# CanLogger_V21.net
KiCad netlist of a schematic drawn in EAGLE
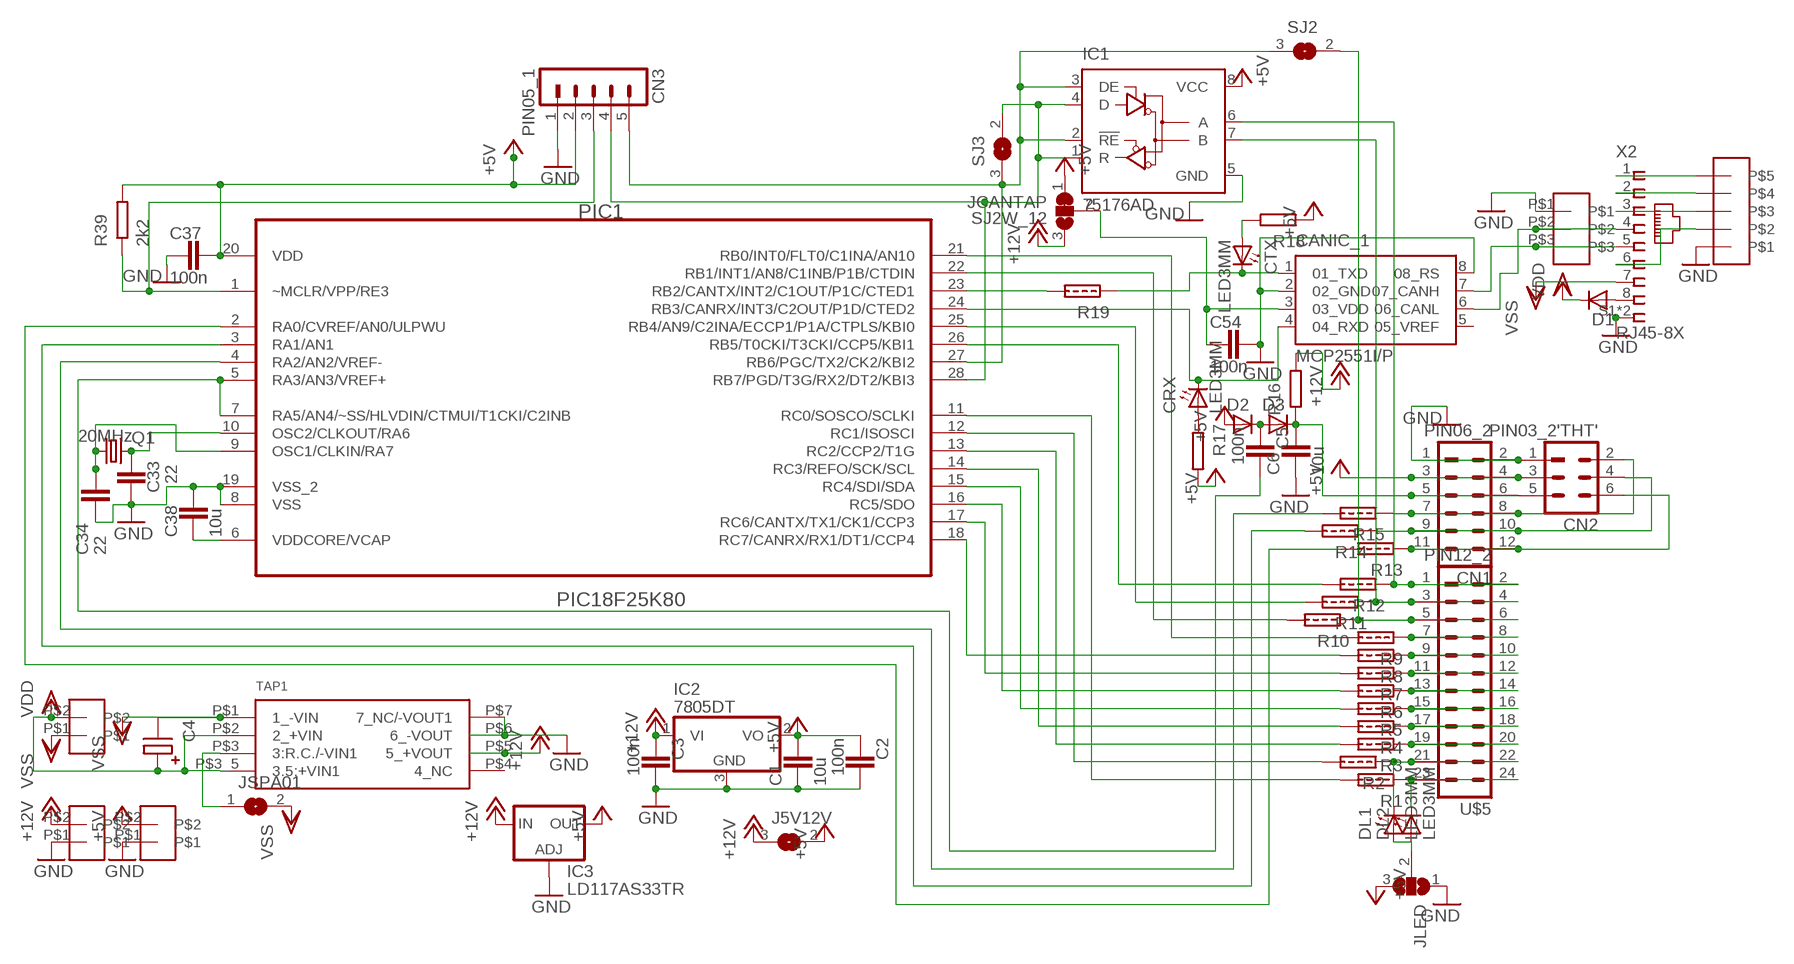
[diagram p0: schematic, sheet 1]

(export (version "E")
  (design (tool "Eeschema 10.0.6"))
  (components
    (comp (ref "C1")
      (value "10u")
      (footprint "eagle-import:R0805")
      (libsource (lib "eagle-import") (part "C0805"))
    )
    (comp (ref "C2")
      (value "100n")
      (footprint "eagle-import:R0805")
      (libsource (lib "eagle-import") (part "C0805"))
    )
    (comp (ref "C3")
      (value "100n")
      (footprint "eagle-import:R0805")
      (libsource (lib "eagle-import") (part "C0805"))
    )
    (comp (ref "C4")
      (value "C_EL1R05")
      (footprint "eagle-import:C_EL1RASZT05")
      (libsource (lib "eagle-import") (part "C_EL1R05"))
    )
    (comp (ref "C5")
      (value "100n")
      (footprint "eagle-import:R0805")
      (libsource (lib "eagle-import") (part "C0805"))
    )
    (comp (ref "C6")
      (value "10u")
      (footprint "eagle-import:R0805")
      (libsource (lib "eagle-import") (part "C0805"))
    )
    (comp (ref "C33")
      (value "22")
      (footprint "eagle-import:R0805")
      (libsource (lib "eagle-import") (part "C0805"))
    )
    (comp (ref "C34")
      (value "22")
      (footprint "eagle-import:R0805")
      (libsource (lib "eagle-import") (part "C0805"))
    )
    (comp (ref "C37")
      (value "100n")
      (footprint "eagle-import:R0805")
      (libsource (lib "eagle-import") (part "C0805"))
    )
    (comp (ref "C38")
      (value "10u")
      (footprint "eagle-import:R0805")
      (libsource (lib "eagle-import") (part "C0805"))
    )
    (comp (ref "C54")
      (value "100n")
      (footprint "eagle-import:R0805")
      (libsource (lib "eagle-import") (part "C0805"))
    )
    (comp (ref "CANIC_1")
      (value "MCP2551I/P")
      (footprint "eagle-import:DIL_8")
      (libsource (lib "eagle-import") (part "MCP2551I/P"))
    )
    (comp (ref "CN1")
      (value "PIN06_2")
      (footprint "eagle-import:PIN06_2")
      (libsource (lib "eagle-import") (part "PIN06_2"))
    )
    (comp (ref "CN2")
      (value "PIN03_2'THT'")
      (footprint "eagle-import:PIN03_2")
      (libsource (lib "eagle-import") (part "PIN03_2'THT'"))
    )
    (comp (ref "CN3")
      (value "PIN05_1")
      (footprint "eagle-import:PIN05_1")
      (libsource (lib "eagle-import") (part "PIN05_1"))
    )
    (comp (ref "CN_CAN")
      (value "FEHER_TUS_3")
      (footprint "eagle-import:FEHER_TUS_3")
      (libsource (lib "eagle-import") (part "FEHER_TUS_3"))
    )
    (comp (ref "CRX")
      (value "LED3MM")
      (footprint "eagle-import:LED3MM")
      (libsource (lib "eagle-import") (part "LED3MM"))
    )
    (comp (ref "CTX")
      (value "LED3MM")
      (footprint "eagle-import:LED3MM")
      (libsource (lib "eagle-import") (part "LED3MM"))
    )
    (comp (ref "D1")
      (value "D1RNAGY")
      (footprint "eagle-import:D1RASZTNAGY")
      (libsource (lib "eagle-import") (part "D1RNAGY"))
    )
    (comp (ref "D2")
      (value "D0805")
      (footprint "eagle-import:D0805")
      (libsource (lib "eagle-import") (part "D0805"))
    )
    (comp (ref "D3")
      (value "D0805")
      (footprint "eagle-import:D0805")
      (libsource (lib "eagle-import") (part "D0805"))
    )
    (comp (ref "DL1")
      (value "LED3MM")
      (footprint "eagle-import:LED3MM")
      (libsource (lib "eagle-import") (part "LED3MM"))
    )
    (comp (ref "DL2")
      (value "LED3MM")
      (footprint "eagle-import:LED3MM")
      (libsource (lib "eagle-import") (part "LED3MM"))
    )
    (comp (ref "IC1")
      (value "75176AD")
      (footprint "eagle-import:D_R-PDSO-G8")
      (libsource (lib "eagle-import") (part "75176AD"))
    )
    (comp (ref "IC2")
      (value "7805DT")
      (footprint "eagle-import:TO252")
      (libsource (lib "eagle-import") (part "78DT05"))
    )
    (comp (ref "IC3")
      (value "LD117AS33TR")
      (footprint "eagle-import:SOT223")
      (libsource (lib "eagle-import") (part "LD117A?S33TR"))
    )
    (comp (ref "J5V12V")
      (value "SJ")
      (footprint "eagle-import:SJ")
      (libsource (lib "eagle-import") (part "jumper2_SJ"))
    )
    (comp (ref "JCANTAP")
      (value "SJ2W_12")
      (footprint "eagle-import:SJ2_12")
      (libsource (lib "eagle-import") (part "SJ2W_12"))
    )
    (comp (ref "JLED")
      (value "SJ2W")
      (footprint "eagle-import:SJ2")
      (libsource (lib "eagle-import") (part "SJ2W"))
    )
    (comp (ref "JSPA01")
      (value "SJW")
      (footprint "eagle-import:SJW")
      (libsource (lib "eagle-import") (part "SJW"))
    )
    (comp (ref "PIC1")
      (value "PIC18F25K80")
      (footprint "eagle-import:SOIC127P1030X265-28N")
      (libsource (lib "eagle-import") (part "PIC18F25K80"))
    )
    (comp (ref "Q1")
      (value "20MHz")
      (footprint "eagle-import:XTAL_QS")
      (libsource (lib "eagle-import") (part "XTAL_2QS"))
    )
    (comp (ref "R1")
      (value "RNULL_EU0805")
      (footprint "eagle-import:R0805_C")
      (libsource (lib "eagle-import") (part "RNULL_EU0805"))
    )
    (comp (ref "R2")
      (value "RNULL_EU0805")
      (footprint "eagle-import:R0805_C")
      (libsource (lib "eagle-import") (part "RNULL_EU0805"))
    )
    (comp (ref "R3")
      (value "RNULL_EU0805")
      (footprint "eagle-import:R0805_C")
      (libsource (lib "eagle-import") (part "RNULL_EU0805"))
    )
    (comp (ref "R4")
      (value "RNULL_EU0805")
      (footprint "eagle-import:R0805_C")
      (libsource (lib "eagle-import") (part "RNULL_EU0805"))
    )
    (comp (ref "R5")
      (value "RNULL_EU0805")
      (footprint "eagle-import:R0805_C")
      (libsource (lib "eagle-import") (part "RNULL_EU0805"))
    )
    (comp (ref "R6")
      (value "RNULL_EU0805")
      (footprint "eagle-import:R0805_C")
      (libsource (lib "eagle-import") (part "RNULL_EU0805"))
    )
    (comp (ref "R7")
      (value "RNULL_EU0805")
      (footprint "eagle-import:R0805_C")
      (libsource (lib "eagle-import") (part "RNULL_EU0805"))
    )
    (comp (ref "R8")
      (value "RNULL_EU0805")
      (footprint "eagle-import:R0805_C")
      (libsource (lib "eagle-import") (part "RNULL_EU0805"))
    )
    (comp (ref "R9")
      (value "RNULL_EU0805")
      (footprint "eagle-import:R0805_C")
      (libsource (lib "eagle-import") (part "RNULL_EU0805"))
    )
    (comp (ref "R10")
      (value "RNULL_EU0805")
      (footprint "eagle-import:R0805_C")
      (libsource (lib "eagle-import") (part "RNULL_EU0805"))
    )
    (comp (ref "R11")
      (value "RNULL_EU0805")
      (footprint "eagle-import:R0805_C")
      (libsource (lib "eagle-import") (part "RNULL_EU0805"))
    )
    (comp (ref "R12")
      (value "RNULL_EU0805")
      (footprint "eagle-import:R0805_C")
      (libsource (lib "eagle-import") (part "RNULL_EU0805"))
    )
    (comp (ref "R13")
      (value "RNULL_EU0805")
      (footprint "eagle-import:R0805_C")
      (libsource (lib "eagle-import") (part "RNULL_EU0805"))
    )
    (comp (ref "R14")
      (value "RNULL_EU0805")
      (footprint "eagle-import:R0805_C")
      (libsource (lib "eagle-import") (part "RNULL_EU0805"))
    )
    (comp (ref "R15")
      (value "RNULL_EU0805")
      (footprint "eagle-import:R0805_C")
      (libsource (lib "eagle-import") (part "RNULL_EU0805"))
    )
    (comp (ref "R16")
      (value "R_EU0805")
      (footprint "eagle-import:R0805")
      (libsource (lib "eagle-import") (part "R_EU0805"))
    )
    (comp (ref "R17")
      (value "R_EU0805")
      (footprint "eagle-import:R0805")
      (libsource (lib "eagle-import") (part "R_EU0805"))
    )
    (comp (ref "R18")
      (value "R_EU0805")
      (footprint "eagle-import:R0805")
      (libsource (lib "eagle-import") (part "R_EU0805"))
    )
    (comp (ref "R19")
      (value "RNULL_EU0805")
      (footprint "eagle-import:R0805_C")
      (libsource (lib "eagle-import") (part "RNULL_EU0805"))
    )
    (comp (ref "R39")
      (value "2k2")
      (footprint "eagle-import:R0805")
      (libsource (lib "eagle-import") (part "R_EU0805"))
    )
    (comp (ref "SJ2")
      (value "SJ")
      (footprint "eagle-import:SJ")
      (libsource (lib "eagle-import") (part "jumper2_SJ"))
    )
    (comp (ref "SJ3")
      (value "SJ")
      (footprint "eagle-import:SJ")
      (libsource (lib "eagle-import") (part "jumper2_SJ"))
    )
    (comp (ref "TAP1")
      (value "SPA01_02C")
      (footprint "eagle-import:SPA01_02C")
      (libsource (lib "eagle-import") (part "SPA01_02C"))
    )
    (comp (ref "U$1")
      (value "FEHER_TUS_5")
      (footprint "eagle-import:FEHER_TUS_5")
      (libsource (lib "eagle-import") (part "FEHER_TUS_5"))
    )
    (comp (ref "U$2")
      (value "FEHER_TUS_2ALLO")
      (footprint "eagle-import:FEHER_TUS_2")
      (libsource (lib "eagle-import") (part "FEHER_TUS_2ALLO"))
    )
    (comp (ref "U$3")
      (value "FEHER_TUS_2ALLO")
      (footprint "eagle-import:FEHER_TUS_2")
      (libsource (lib "eagle-import") (part "FEHER_TUS_2ALLO"))
    )
    (comp (ref "U$4")
      (value "FEHER_TUS_2ALLO")
      (footprint "eagle-import:FEHER_TUS_2")
      (libsource (lib "eagle-import") (part "FEHER_TUS_2ALLO"))
    )
    (comp (ref "U$5")
      (value "PIN12_2")
      (footprint "eagle-import:PIN12_2")
      (libsource (lib "eagle-import") (part "PIN12_2"))
    )
    (comp (ref "X2")
      (value "RJ45-8X")
      (footprint "eagle-import:RJ45")
      (libsource (lib "eagle-import") (part "RJ45-8X"))
    )
  )
  (nets
    (net (code "1") (name "+5V") (class "Default")
      (node (ref "C1") (pin "1") (pinfunction "1_1") (pintype "passive"))
      (node (ref "C2") (pin "2") (pinfunction "2_2") (pintype "passive"))
      (node (ref "C37") (pin "1") (pinfunction "1_1") (pintype "passive"))
      (node (ref "CN1") (pin "3") (pinfunction "3_3") (pintype "passive"))
      (node (ref "CN1") (pin "4") (pinfunction "4_4") (pintype "passive"))
      (node (ref "CN2") (pin "3") (pinfunction "3_3") (pintype "passive"))
      (node (ref "CN3") (pin "2") (pinfunction "2_2") (pintype "passive"))
      (node (ref "D2") (pin "1") (pinfunction "A_1") (pintype "passive"))
      (node (ref "IC1") (pin "8") (pinfunction "VCC_8") (pintype "power_in"))
      (node (ref "IC2") (pin "2") (pinfunction "VO_2") (pintype "passive"))
      (node (ref "IC3") (pin "2") (pinfunction "OUT_2") (pintype "passive"))
      (node (ref "IC3") (pin "4") (pinfunction "OUT_4") (pintype "passive"))
      (node (ref "J5V12V") (pin "2") (pinfunction "2_2") (pintype "passive"))
      (node (ref "JCANTAP") (pin "1") (pinfunction "1_1") (pintype "passive"))
      (node (ref "JLED") (pin "3") (pinfunction "3_3") (pintype "passive"))
      (node (ref "PIC1") (pin "20") (pinfunction "VDD_20") (pintype "power_in"))
      (node (ref "R17") (pin "2") (pinfunction "E_2") (pintype "passive"))
      (node (ref "R18") (pin "1") (pinfunction "A_1") (pintype "passive"))
      (node (ref "R39") (pin "2") (pinfunction "E_2") (pintype "passive"))
      (node (ref "U$4") (pin "P$2") (pinfunction "P$2_P$2") (pintype "bidirectional"))
    )
    (net (code "2") (name "+12V") (class "Default")
      (node (ref "C3") (pin "2") (pinfunction "2_2") (pintype "passive"))
      (node (ref "IC2") (pin "1") (pinfunction "VI_1") (pintype "input"))
      (node (ref "IC3") (pin "3") (pinfunction "IN_3") (pintype "input"))
      (node (ref "J5V12V") (pin "3") (pinfunction "1_3") (pintype "passive"))
      (node (ref "JCANTAP") (pin "3") (pinfunction "3_3") (pintype "passive"))
      (node (ref "R16") (pin "2") (pinfunction "E_2") (pintype "passive"))
      (node (ref "TAP1") (pin "P$5") (pinfunction "5_+VOUT_P$5") (pintype "bidirectional"))
      (node (ref "U$3") (pin "P$2") (pinfunction "P$2_P$2") (pintype "bidirectional"))
    )
    (net (code "3") (name "GND") (class "Default")
      (node (ref "C1") (pin "2") (pinfunction "2_2") (pintype "passive"))
      (node (ref "C2") (pin "1") (pinfunction "1_1") (pintype "passive"))
      (node (ref "C3") (pin "1") (pinfunction "1_1") (pintype "passive"))
      (node (ref "C33") (pin "2") (pinfunction "2_2") (pintype "passive"))
      (node (ref "C34") (pin "2") (pinfunction "2_2") (pintype "passive"))
      (node (ref "C37") (pin "2") (pinfunction "2_2") (pintype "passive"))
      (node (ref "C38") (pin "1") (pinfunction "1_1") (pintype "passive"))
      (node (ref "C54") (pin "1") (pinfunction "1_1") (pintype "passive"))
      (node (ref "C6") (pin "2") (pinfunction "2_2") (pintype "passive"))
      (node (ref "CANIC_1") (pin "2") (pinfunction "02_GND_2") (pintype "power_in"))
      (node (ref "CANIC_1") (pin "8") (pinfunction "08_RS_8") (pintype "input"))
      (node (ref "CN1") (pin "1") (pinfunction "1_1") (pintype "passive"))
      (node (ref "CN1") (pin "2") (pinfunction "2_2") (pintype "passive"))
      (node (ref "CN2") (pin "1") (pinfunction "1_1") (pintype "passive"))
      (node (ref "CN3") (pin "1") (pinfunction "1_1") (pintype "passive"))
      (node (ref "CN_CAN") (pin "P$1") (pinfunction "P$1_P$1") (pintype "bidirectional"))
      (node (ref "IC1") (pin "5") (pinfunction "GND_5") (pintype "power_in"))
      (node (ref "IC2") (pin "3") (pinfunction "GND_3") (pintype "passive"))
      (node (ref "IC3") (pin "1") (pinfunction "ADJ_1") (pintype "input"))
      (node (ref "JLED") (pin "1") (pinfunction "1_1") (pintype "passive"))
      (node (ref "PIC1") (pin "19") (pinfunction "VSS_2_19") (pintype "power_in"))
      (node (ref "PIC1") (pin "8") (pinfunction "VSS_8") (pintype "power_in"))
      (node (ref "TAP1") (pin "P$6") (pinfunction "6_-VOUT_P$6") (pintype "bidirectional"))
      (node (ref "TAP1") (pin "P$7") (pinfunction "7_NC/-VOUT1_P$7") (pintype "bidirectional"))
      (node (ref "U$1") (pin "P$1") (pinfunction "P$1_P$1") (pintype "bidirectional"))
      (node (ref "U$3") (pin "P$1") (pinfunction "P$1_P$1") (pintype "bidirectional"))
      (node (ref "U$4") (pin "P$1") (pinfunction "P$1_P$1") (pintype "bidirectional"))
      (node (ref "X2") (pin "S1") (pinfunction "S_S1") (pintype "passive"))
      (node (ref "X2") (pin "S2") (pinfunction "S_S2") (pintype "passive"))
    )
    (net (code "4") (name "Net-(CANIC_1-01_TXD)") (class "Default")
      (node (ref "CANIC_1") (pin "1") (pinfunction "01_TXD_1") (pintype "input"))
      (node (ref "CTX") (pin "K") (pinfunction "C_K") (pintype "passive"))
      (node (ref "R19") (pin "1") (pinfunction "A_1") (pintype "passive"))
    )
    (net (code "5") (name "Net-(CANIC_1-03_VDD)") (class "Default")
      (node (ref "C54") (pin "2") (pinfunction "2_2") (pintype "passive"))
      (node (ref "CANIC_1") (pin "3") (pinfunction "03_VDD_3") (pintype "power_in"))
      (node (ref "JCANTAP") (pin "2") (pinfunction "2_2") (pintype "passive"))
    )
    (net (code "6") (name "Net-(CANIC_1-04_RXD)") (class "Default")
      (node (ref "CANIC_1") (pin "4") (pinfunction "04_RXD_4") (pintype "output"))
      (node (ref "CRX") (pin "K") (pinfunction "C_K") (pintype "passive"))
      (node (ref "PIC1") (pin "24") (pinfunction "RB3/CANRX/INT3/C2OUT/P1D/CTED2_24") (pintype "bidirectional"))
    )
    (net (code "7") (name "Net-(CANIC_1-06_CANL)") (class "Default")
      (node (ref "CANIC_1") (pin "6") (pinfunction "06_CANL_6") (pintype "bidirectional"))
      (node (ref "CN_CAN") (pin "P$2") (pinfunction "P$2_P$2") (pintype "bidirectional"))
      (node (ref "X2") (pin "4") (pinfunction "4_4") (pintype "passive"))
    )
    (net (code "8") (name "Net-(CANIC_1-07_CANH)") (class "Default")
      (node (ref "CANIC_1") (pin "7") (pinfunction "07_CANH_7") (pintype "bidirectional"))
      (node (ref "CN_CAN") (pin "P$3") (pinfunction "P$3_P$3") (pintype "bidirectional"))
      (node (ref "X2") (pin "5") (pinfunction "5_5") (pintype "passive"))
    )
    (net (code "9") (name "Net-(D1-A)") (class "Default")
      (node (ref "D1") (pin "P$1") (pinfunction "A_P$1") (pintype "passive"))
      (node (ref "X2") (pin "8") (pinfunction "8_8") (pintype "passive"))
    )
    (net (code "10") (name "Net-(D2-C)") (class "Default")
      (node (ref "C5") (pin "2") (pinfunction "2_2") (pintype "passive"))
      (node (ref "D2") (pin "2") (pinfunction "C_2") (pintype "passive"))
      (node (ref "D3") (pin "1") (pinfunction "A_1") (pintype "passive"))
    )
    (net (code "11") (name "Net-(D3-C)") (class "Default")
      (node (ref "C6") (pin "1") (pinfunction "1_1") (pintype "passive"))
      (node (ref "CN1") (pin "5") (pinfunction "5_5") (pintype "passive"))
      (node (ref "CN1") (pin "6") (pinfunction "6_6") (pintype "passive"))
      (node (ref "CN2") (pin "5") (pinfunction "5_5") (pintype "passive"))
      (node (ref "D3") (pin "2") (pinfunction "C_2") (pintype "passive"))
      (node (ref "R16") (pin "1") (pinfunction "A_1") (pintype "passive"))
    )
    (net (code "12") (name "Net-(DL1-C)") (class "Default")
      (node (ref "DL1") (pin "K") (pinfunction "C_K") (pintype "passive"))
      (node (ref "R2") (pin "1") (pinfunction "A_1") (pintype "passive"))
      (node (ref "U$5") (pin "21") (pinfunction "21_21") (pintype "passive"))
      (node (ref "U$5") (pin "22") (pinfunction "22_22") (pintype "passive"))
    )
    (net (code "13") (name "Net-(DL1-PadA)") (class "Default")
      (node (ref "DL1") (pin "A") (pinfunction "A_A") (pintype "passive"))
      (node (ref "DL2") (pin "A") (pinfunction "A_A") (pintype "passive"))
      (node (ref "JLED") (pin "2") (pinfunction "2_2") (pintype "passive"))
    )
    (net (code "14") (name "Net-(DL2-C)") (class "Default")
      (node (ref "DL2") (pin "K") (pinfunction "C_K") (pintype "passive"))
      (node (ref "R1") (pin "1") (pinfunction "A_1") (pintype "passive"))
      (node (ref "U$5") (pin "23") (pinfunction "23_23") (pintype "passive"))
      (node (ref "U$5") (pin "24") (pinfunction "24_24") (pintype "passive"))
    )
    (net (code "15") (name "Net-(IC1-A)") (class "Default")
      (node (ref "IC1") (pin "6") (pinfunction "A_6") (pintype "output"))
      (node (ref "R12") (pin "1") (pinfunction "A_1") (pintype "passive"))
      (node (ref "U$5") (pin "1") (pinfunction "1_1") (pintype "passive"))
      (node (ref "U$5") (pin "2") (pinfunction "2_2") (pintype "passive"))
    )
    (net (code "16") (name "Net-(IC1-B)") (class "Default")
      (node (ref "IC1") (pin "7") (pinfunction "B_7") (pintype "output"))
      (node (ref "R11") (pin "1") (pinfunction "A_1") (pintype "passive"))
      (node (ref "U$5") (pin "3") (pinfunction "3_3") (pintype "passive"))
      (node (ref "U$5") (pin "4") (pinfunction "4_4") (pintype "passive"))
    )
    (net (code "17") (name "Net-(IC1-D)") (class "Default")
      (node (ref "CN3") (pin "4") (pinfunction "4_4") (pintype "passive"))
      (node (ref "IC1") (pin "1") (pinfunction "R_1") (pintype "input"))
      (node (ref "IC1") (pin "4") (pinfunction "D_4") (pintype "input"))
      (node (ref "PIC1") (pin "28") (pinfunction "RB7/PGD/T3G/RX2/DT2/KBI3_28") (pintype "bidirectional"))
      (node (ref "SJ3") (pin "2") (pinfunction "2_2") (pintype "passive"))
    )
    (net (code "18") (name "Net-(IC1-DE)") (class "Default")
      (node (ref "CN3") (pin "5") (pinfunction "5_5") (pintype "passive"))
      (node (ref "IC1") (pin "2") (pinfunction "~{RE}_2") (pintype "input"))
      (node (ref "IC1") (pin "3") (pinfunction "DE_3") (pintype "input"))
      (node (ref "PIC1") (pin "27") (pinfunction "RB6/PGC/TX2/CK2/KBI2_27") (pintype "bidirectional"))
      (node (ref "SJ2") (pin "3") (pinfunction "1_3") (pintype "passive"))
      (node (ref "SJ3") (pin "3") (pinfunction "1_3") (pintype "passive"))
    )
    (net (code "19") (name "Net-(PIC1-OSC1{slash}CLKIN{slash}RA7)") (class "Default")
      (node (ref "C34") (pin "1") (pinfunction "1_1") (pintype "passive"))
      (node (ref "PIC1") (pin "9") (pinfunction "OSC1/CLKIN/RA7_9") (pintype "bidirectional"))
      (node (ref "Q1") (pin "1") (pinfunction "1_1") (pintype "passive"))
    )
    (net (code "20") (name "Net-(PIC1-OSC2{slash}CLKOUT{slash}RA6)") (class "Default")
      (node (ref "C33") (pin "1") (pinfunction "1_1") (pintype "passive"))
      (node (ref "PIC1") (pin "10") (pinfunction "OSC2/CLKOUT/RA6_10") (pintype "bidirectional"))
      (node (ref "Q1") (pin "2") (pinfunction "2_2") (pintype "passive"))
    )
    (net (code "21") (name "Net-(PIC1-RA0{slash}CVREF{slash}AN0{slash}ULPWU)") (class "Default")
      (node (ref "PIC1") (pin "2") (pinfunction "RA0/CVREF/AN0/ULPWU_2") (pintype "bidirectional"))
      (node (ref "R13") (pin "2") (pinfunction "E_2") (pintype "passive"))
    )
    (net (code "22") (name "Net-(PIC1-RA1{slash}AN1)") (class "Default")
      (node (ref "PIC1") (pin "3") (pinfunction "RA1/AN1_3") (pintype "bidirectional"))
      (node (ref "R14") (pin "2") (pinfunction "E_2") (pintype "passive"))
    )
    (net (code "23") (name "Net-(PIC1-RA2{slash}AN2{slash}VREF-)") (class "Default")
      (node (ref "PIC1") (pin "4") (pinfunction "RA2/AN2/VREF-_4") (pintype "bidirectional"))
      (node (ref "R15") (pin "2") (pinfunction "E_2") (pintype "passive"))
    )
    (net (code "24") (name "Net-(PIC1-RA3{slash}AN3{slash}VREF+)") (class "Default")
      (node (ref "C5") (pin "1") (pinfunction "1_1") (pintype "passive"))
      (node (ref "PIC1") (pin "5") (pinfunction "RA3/AN3/VREF+_5") (pintype "bidirectional"))
      (node (ref "PIC1") (pin "7") (pinfunction "RA5/AN4/~{SS/HLVDIN/CTMUI/T1CKI/C2INB}_7") (pintype "bidirectional"))
    )
    (net (code "25") (name "Net-(PIC1-RB0{slash}INT0{slash}FLT0{slash}C1INA{slash}AN10)") (class "Default")
      (node (ref "PIC1") (pin "21") (pinfunction "RB0/INT0/FLT0/C1INA/AN10_21") (pintype "bidirectional"))
      (node (ref "R9") (pin "2") (pinfunction "E_2") (pintype "passive"))
    )
    (net (code "26") (name "Net-(PIC1-RB1{slash}INT1{slash}AN8{slash}C1INB{slash}P1B{slash}CTDIN)") (class "Default")
      (node (ref "PIC1") (pin "22") (pinfunction "RB1/INT1/AN8/C1INB/P1B/CTDIN_22") (pintype "bidirectional"))
      (node (ref "R10") (pin "2") (pinfunction "E_2") (pintype "passive"))
    )
    (net (code "27") (name "Net-(PIC1-RB2{slash}CANTX{slash}INT2{slash}C1OUT{slash}P1C{slash}CTED1)") (class "Default")
      (node (ref "PIC1") (pin "23") (pinfunction "RB2/CANTX/INT2/C1OUT/P1C/CTED1_23") (pintype "bidirectional"))
      (node (ref "R19") (pin "2") (pinfunction "E_2") (pintype "passive"))
    )
    (net (code "28") (name "Net-(PIC1-RB4{slash}AN9{slash}C2INA{slash}ECCP1{slash}P1A{slash}CTPLS{slash}KBI0)") (class "Default")
      (node (ref "PIC1") (pin "25") (pinfunction "RB4/AN9/C2INA/ECCP1/P1A/CTPLS/KBI0_25") (pintype "bidirectional"))
      (node (ref "R11") (pin "2") (pinfunction "E_2") (pintype "passive"))
    )
    (net (code "29") (name "Net-(PIC1-RB5{slash}T0CKI{slash}T3CKI{slash}CCP5{slash}KBI1)") (class "Default")
      (node (ref "PIC1") (pin "26") (pinfunction "RB5/T0CKI/T3CKI/CCP5/KBI1_26") (pintype "bidirectional"))
      (node (ref "R12") (pin "2") (pinfunction "E_2") (pintype "passive"))
    )
    (net (code "30") (name "Net-(PIC1-RC0{slash}SOSCO{slash}SCLKI)") (class "Default")
      (node (ref "PIC1") (pin "11") (pinfunction "RC0/SOSCO/SCLKI_11") (pintype "bidirectional"))
      (node (ref "R1") (pin "2") (pinfunction "E_2") (pintype "passive"))
    )
    (net (code "31") (name "Net-(PIC1-RC1{slash}ISOSCI)") (class "Default")
      (node (ref "PIC1") (pin "12") (pinfunction "RC1/ISOSCI_12") (pintype "bidirectional"))
      (node (ref "R2") (pin "2") (pinfunction "E_2") (pintype "passive"))
    )
    (net (code "32") (name "Net-(PIC1-RC2{slash}CCP2{slash}T1G)") (class "Default")
      (node (ref "PIC1") (pin "13") (pinfunction "RC2/CCP2/T1G_13") (pintype "bidirectional"))
      (node (ref "R3") (pin "2") (pinfunction "E_2") (pintype "passive"))
    )
    (net (code "33") (name "Net-(PIC1-RC3{slash}REFO{slash}SCK{slash}SCL)") (class "Default")
      (node (ref "PIC1") (pin "14") (pinfunction "RC3/REFO/SCK/SCL_14") (pintype "bidirectional"))
      (node (ref "R4") (pin "2") (pinfunction "E_2") (pintype "passive"))
    )
    (net (code "34") (name "Net-(PIC1-RC4{slash}SDI{slash}SDA)") (class "Default")
      (node (ref "PIC1") (pin "15") (pinfunction "RC4/SDI/SDA_15") (pintype "bidirectional"))
      (node (ref "R5") (pin "2") (pinfunction "E_2") (pintype "passive"))
    )
    (net (code "35") (name "Net-(PIC1-RC5{slash}SDO)") (class "Default")
      (node (ref "PIC1") (pin "16") (pinfunction "RC5/SDO_16") (pintype "bidirectional"))
      (node (ref "R6") (pin "2") (pinfunction "E_2") (pintype "passive"))
    )
    (net (code "36") (name "Net-(PIC1-RC6{slash}CANTX{slash}TX1{slash}CK1{slash}CCP3)") (class "Default")
      (node (ref "PIC1") (pin "17") (pinfunction "RC6/CANTX/TX1/CK1/CCP3_17") (pintype "bidirectional"))
      (node (ref "R7") (pin "2") (pinfunction "E_2") (pintype "passive"))
    )
    (net (code "37") (name "Net-(PIC1-RC7{slash}CANRX{slash}RX1{slash}DT1{slash}CCP4)") (class "Default")
      (node (ref "PIC1") (pin "18") (pinfunction "RC7/CANRX/RX1/DT1/CCP4_18") (pintype "bidirectional"))
      (node (ref "R8") (pin "2") (pinfunction "E_2") (pintype "passive"))
    )
    (net (code "38") (name "Net-(PIC1-VDDCORE{slash}VCAP)") (class "Default")
      (node (ref "C38") (pin "2") (pinfunction "2_2") (pintype "passive"))
      (node (ref "PIC1") (pin "6") (pinfunction "VDDCORE/VCAP_6") (pintype "bidirectional"))
    )
    (net (code "39") (name "Net-(PIC1-~{MCLR{slash}VPP{slash}RE3})") (class "Default")
      (node (ref "CN3") (pin "3") (pinfunction "3_3") (pintype "passive"))
      (node (ref "PIC1") (pin "1") (pinfunction "~{MCLR/VPP/RE3}_1") (pintype "input"))
      (node (ref "R39") (pin "1") (pinfunction "A_1") (pintype "passive"))
    )
    (net (code "40") (name "Net-(R3-A)") (class "Default")
      (node (ref "R3") (pin "1") (pinfunction "A_1") (pintype "passive"))
      (node (ref "U$5") (pin "19") (pinfunction "19_19") (pintype "passive"))
      (node (ref "U$5") (pin "20") (pinfunction "20_20") (pintype "passive"))
    )
    (net (code "41") (name "Net-(R4-A)") (class "Default")
      (node (ref "R4") (pin "1") (pinfunction "A_1") (pintype "passive"))
      (node (ref "U$5") (pin "17") (pinfunction "17_17") (pintype "passive"))
      (node (ref "U$5") (pin "18") (pinfunction "18_18") (pintype "passive"))
    )
    (net (code "42") (name "Net-(R5-A)") (class "Default")
      (node (ref "R5") (pin "1") (pinfunction "A_1") (pintype "passive"))
      (node (ref "U$5") (pin "15") (pinfunction "15_15") (pintype "passive"))
      (node (ref "U$5") (pin "16") (pinfunction "16_16") (pintype "passive"))
    )
    (net (code "43") (name "Net-(R6-A)") (class "Default")
      (node (ref "R6") (pin "1") (pinfunction "A_1") (pintype "passive"))
      (node (ref "U$5") (pin "13") (pinfunction "13_13") (pintype "passive"))
      (node (ref "U$5") (pin "14") (pinfunction "14_14") (pintype "passive"))
    )
    (net (code "44") (name "Net-(R7-A)") (class "Default")
      (node (ref "R7") (pin "1") (pinfunction "A_1") (pintype "passive"))
      (node (ref "U$5") (pin "11") (pinfunction "11_11") (pintype "passive"))
      (node (ref "U$5") (pin "12") (pinfunction "12_12") (pintype "passive"))
    )
    (net (code "45") (name "Net-(R8-A)") (class "Default")
      (node (ref "R8") (pin "1") (pinfunction "A_1") (pintype "passive"))
      (node (ref "U$5") (pin "10") (pinfunction "10_10") (pintype "passive"))
      (node (ref "U$5") (pin "9") (pinfunction "9_9") (pintype "passive"))
    )
    (net (code "46") (name "Net-(R9-A)") (class "Default")
      (node (ref "R9") (pin "1") (pinfunction "A_1") (pintype "passive"))
      (node (ref "U$5") (pin "7") (pinfunction "7_7") (pintype "passive"))
      (node (ref "U$5") (pin "8") (pinfunction "8_8") (pintype "passive"))
    )
    (net (code "47") (name "Net-(R10-A)") (class "Default")
      (node (ref "R10") (pin "1") (pinfunction "A_1") (pintype "passive"))
      (node (ref "SJ2") (pin "2") (pinfunction "2_2") (pintype "passive"))
      (node (ref "U$5") (pin "5") (pinfunction "5_5") (pintype "passive"))
      (node (ref "U$5") (pin "6") (pinfunction "6_6") (pintype "passive"))
    )
    (net (code "48") (name "Net-(R13-A)") (class "Default")
      (node (ref "CN1") (pin "11") (pinfunction "11_11") (pintype "passive"))
      (node (ref "CN1") (pin "12") (pinfunction "12_12") (pintype "passive"))
      (node (ref "CN2") (pin "6") (pinfunction "6_6") (pintype "passive"))
      (node (ref "R13") (pin "1") (pinfunction "A_1") (pintype "passive"))
    )
    (net (code "49") (name "Net-(R14-A)") (class "Default")
      (node (ref "CN1") (pin "10") (pinfunction "10_10") (pintype "passive"))
      (node (ref "CN1") (pin "9") (pinfunction "9_9") (pintype "passive"))
      (node (ref "CN2") (pin "4") (pinfunction "4_4") (pintype "passive"))
      (node (ref "R14") (pin "1") (pinfunction "A_1") (pintype "passive"))
    )
    (net (code "50") (name "Net-(R15-A)") (class "Default")
      (node (ref "CN1") (pin "7") (pinfunction "7_7") (pintype "passive"))
      (node (ref "CN1") (pin "8") (pinfunction "8_8") (pintype "passive"))
      (node (ref "CN2") (pin "2") (pinfunction "2_2") (pintype "passive"))
      (node (ref "R15") (pin "1") (pinfunction "A_1") (pintype "passive"))
    )
    (net (code "51") (name "Net-(R17-A)") (class "Default")
      (node (ref "CRX") (pin "A") (pinfunction "A_A") (pintype "passive"))
      (node (ref "R17") (pin "1") (pinfunction "A_1") (pintype "passive"))
    )
    (net (code "52") (name "Net-(R18-E)") (class "Default")
      (node (ref "CTX") (pin "A") (pinfunction "A_A") (pintype "passive"))
      (node (ref "R18") (pin "2") (pinfunction "E_2") (pintype "passive"))
    )
    (net (code "53") (name "Net-(TAP1-3:R.C.{slash}-VIN1)") (class "Default")
      (node (ref "JSPA01") (pin "1") (pinfunction "1_1") (pintype "passive"))
      (node (ref "TAP1") (pin "P$3") (pinfunction "3:R.C./-VIN1_P$3") (pintype "bidirectional"))
    )
    (net (code "54") (name "Net-(U$1-PadP$2)") (class "Default")
      (node (ref "U$1") (pin "P$2") (pinfunction "P$2_P$2") (pintype "bidirectional"))
      (node (ref "X2") (pin "6") (pinfunction "6_6") (pintype "passive"))
    )
    (net (code "55") (name "Net-(U$1-PadP$3)") (class "Default")
      (node (ref "U$1") (pin "P$3") (pinfunction "P$3_P$3") (pintype "bidirectional"))
      (node (ref "X2") (pin "3") (pinfunction "3_3") (pintype "passive"))
    )
    (net (code "56") (name "Net-(U$1-PadP$4)") (class "Default")
      (node (ref "U$1") (pin "P$4") (pinfunction "P$4_P$4") (pintype "bidirectional"))
      (node (ref "X2") (pin "2") (pinfunction "2_2") (pintype "passive"))
    )
    (net (code "57") (name "Net-(U$1-PadP$5)") (class "Default")
      (node (ref "U$1") (pin "P$5") (pinfunction "P$5_P$5") (pintype "bidirectional"))
      (node (ref "X2") (pin "1") (pinfunction "1_1") (pintype "passive"))
    )
    (net (code "58") (name "VDD") (class "Default")
      (node (ref "C4") (pin "P+") (pinfunction "P+_P+") (pintype "passive"))
      (node (ref "D1") (pin "P$2") (pinfunction "C_P$2") (pintype "passive"))
      (node (ref "TAP1") (pin "P$2") (pinfunction "2_+VIN_P$2") (pintype "bidirectional"))
      (node (ref "TAP1") (pin "P$3_5") (pinfunction "3.5:+VIN1_P$3_5") (pintype "bidirectional"))
      (node (ref "U$2") (pin "P$2") (pinfunction "P$2_P$2") (pintype "bidirectional"))
    )
    (net (code "59") (name "VSS") (class "Default")
      (node (ref "C4") (pin "P-") (pinfunction "P-_P-") (pintype "passive"))
      (node (ref "JSPA01") (pin "2") (pinfunction "2_2") (pintype "passive"))
      (node (ref "TAP1") (pin "P$1") (pinfunction "1_-VIN_P$1") (pintype "bidirectional"))
      (node (ref "U$2") (pin "P$1") (pinfunction "P$1_P$1") (pintype "bidirectional"))
      (node (ref "X2") (pin "7") (pinfunction "7_7") (pintype "passive"))
    )
    (net (code "60") (name "unconnected-(CANIC_1-05_VREF-Pad5)") (class "Default")
      (node (ref "CANIC_1") (pin "5") (pinfunction "05_VREF_5") (pintype "input"))
    )
    (net (code "61") (name "unconnected-(TAP1-4_NC-PadP$4)") (class "Default")
      (node (ref "TAP1") (pin "P$4") (pinfunction "4_NC_P$4") (pintype "bidirectional"))
    )
  )
)
